# PCR_Main_ckt.net
KiCad netlist of a schematic drawn in EAGLE
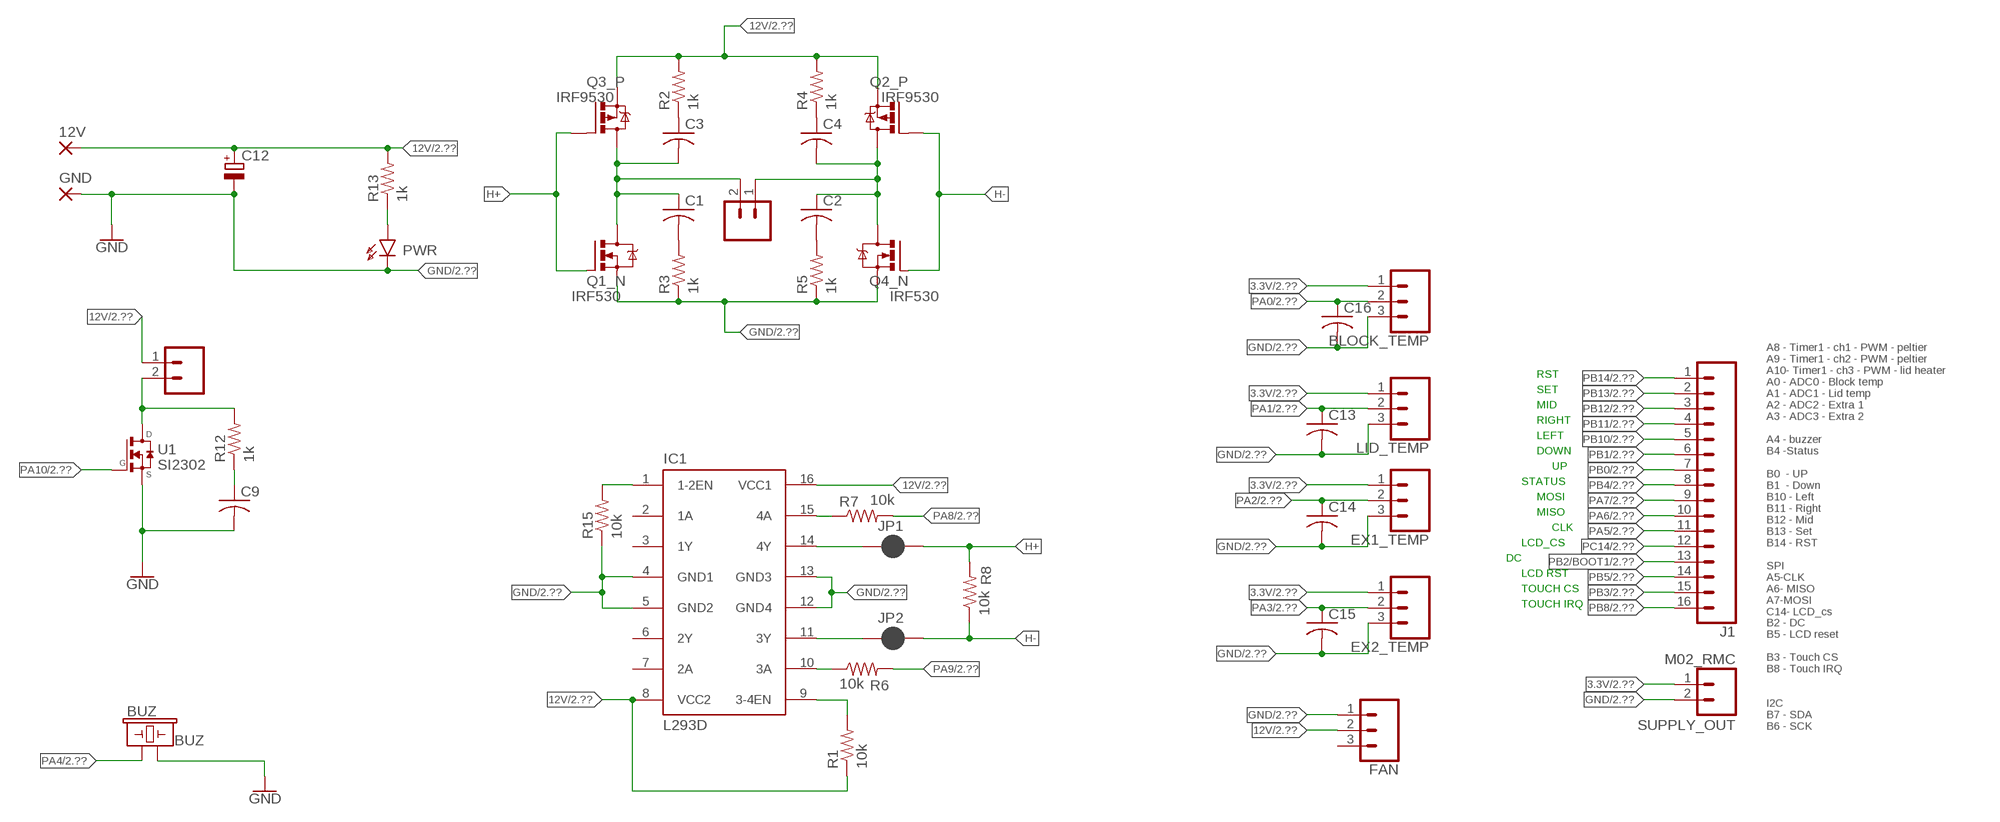
[diagram p0: schematic, sheet 1]
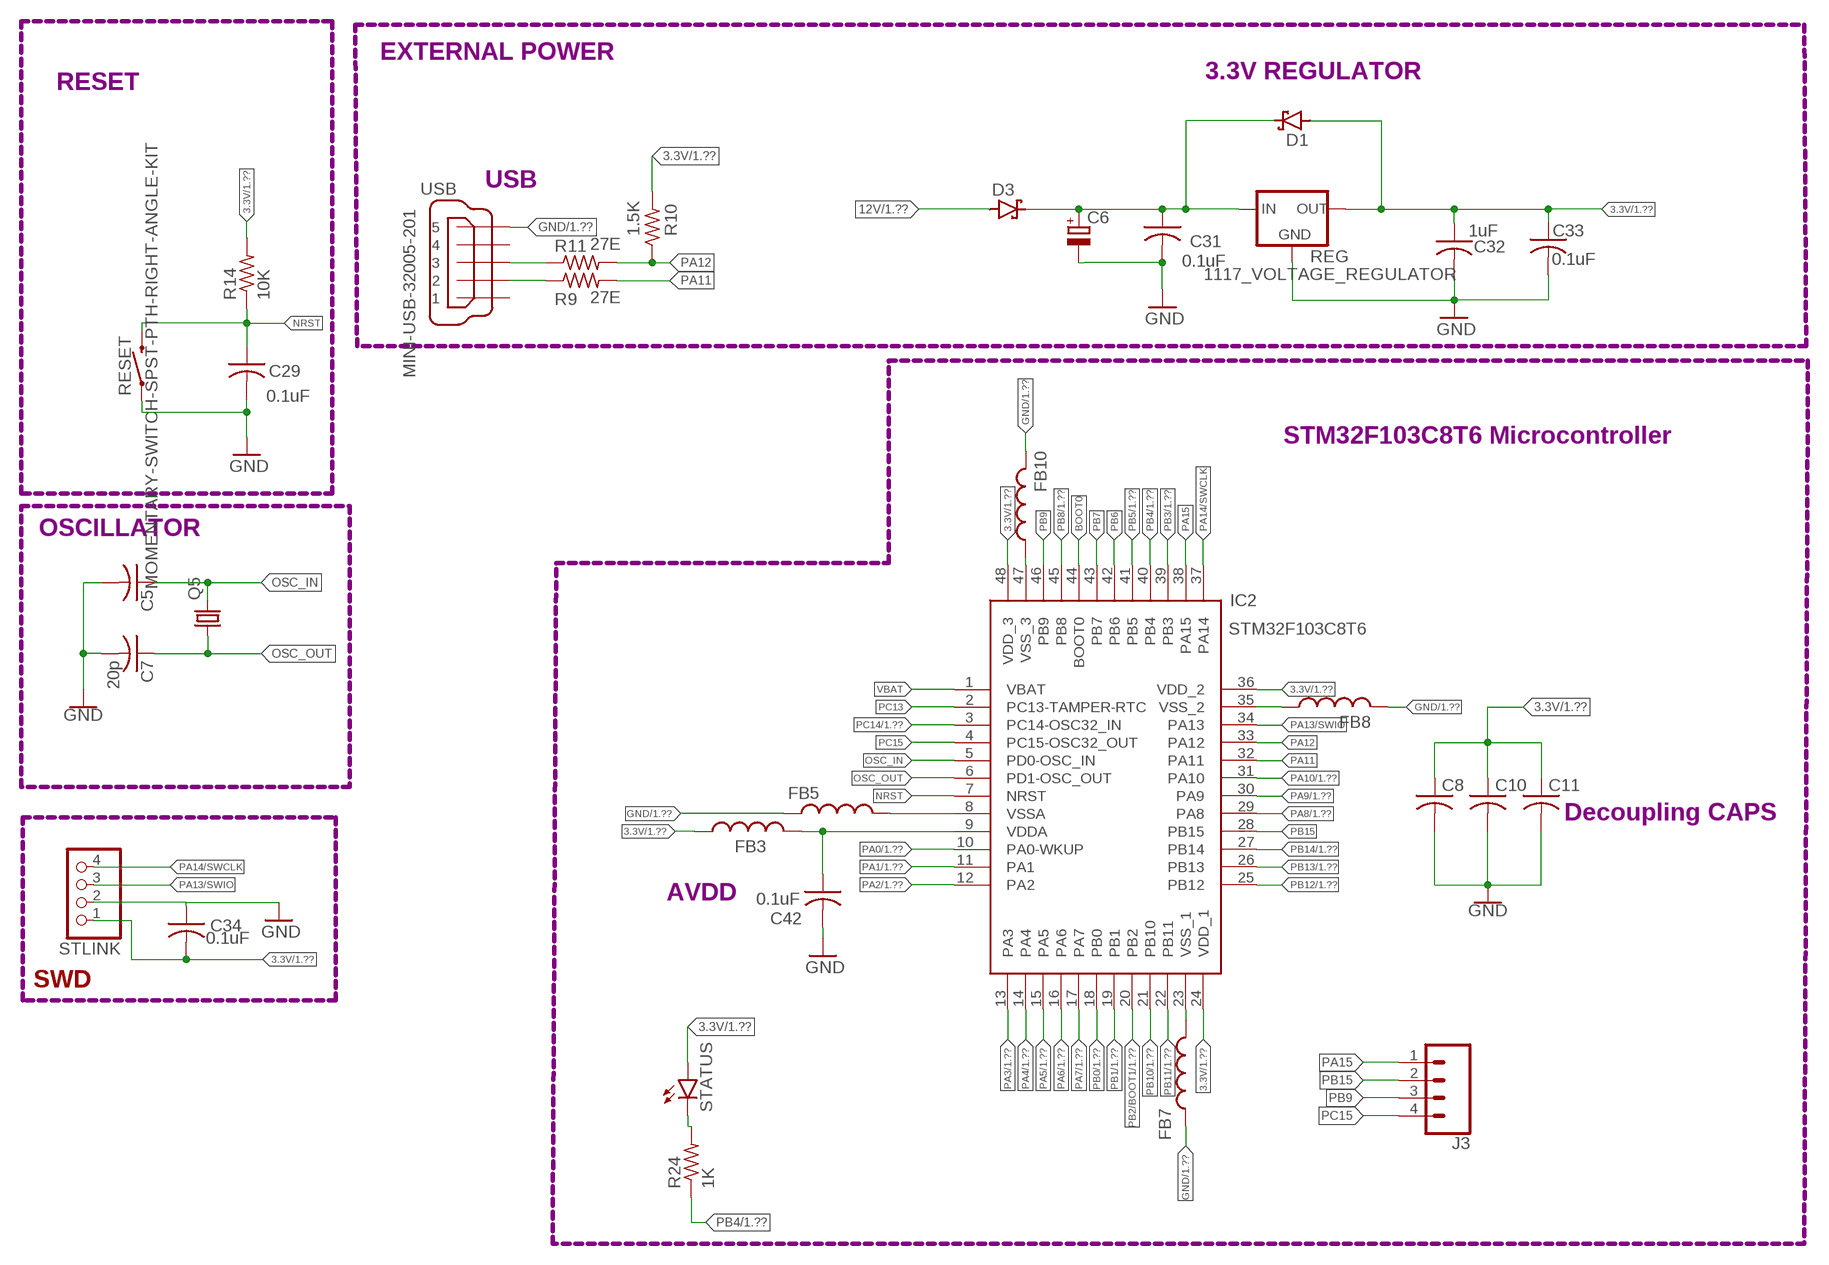
[diagram p1: schematic, sheet 2]

(export (version "E")
  (design (tool "Eeschema 10.0.6"))
  (components
    (comp (ref "+PELTIER-")
      (value "SCREW_TERMINAL_5.08")
      (footprint "eagle-import:SCREW_TERMINAL_5.08")
      (libsource (lib "eagle-import") (part "SCREW_TERMINAL_5.08"))
    )
    (comp (ref "12V")
      (value "WIREPAD4,16O1,6")
      (footprint "eagle-import:4,16O1,6")
      (libsource (lib "eagle-import") (part "WIREPAD4,16O1,6"))
    )
    (comp (ref "BLOCK_TEMP")
      (value "CONN_03")
      (footprint "eagle-import:1X03")
      (libsource (lib "eagle-import") (part "CONN_03"))
    )
    (comp (ref "BUZ")
      (value "BUZ")
      (footprint "eagle-import:BUZZER-12MM")
      (libsource (lib "eagle-import") (part "BUZZER-PTH"))
    )
    (comp (ref "C1")
      (value "C-USC0805")
      (footprint "eagle-import:C0805")
      (libsource (lib "eagle-import") (part "C-USC0805"))
    )
    (comp (ref "C2")
      (value "C-USC0805")
      (footprint "eagle-import:C0805")
      (libsource (lib "eagle-import") (part "C-USC0805"))
    )
    (comp (ref "C3")
      (value "C-USC0805")
      (footprint "eagle-import:C0805")
      (libsource (lib "eagle-import") (part "C-USC0805"))
    )
    (comp (ref "C4")
      (value "C-USC0805")
      (footprint "eagle-import:C0805")
      (libsource (lib "eagle-import") (part "C-USC0805"))
    )
    (comp (ref "C9")
      (value "C-USC0805")
      (footprint "eagle-import:C0805")
      (libsource (lib "eagle-import") (part "C-USC0805"))
    )
    (comp (ref "C12")
      (value "CPOL-EUE5-5")
      (footprint "eagle-import:E5-5")
      (libsource (lib "eagle-import") (part "CPOL-EUE5-5"))
    )
    (comp (ref "C13")
      (value "C-USC0805")
      (footprint "eagle-import:C0805")
      (libsource (lib "eagle-import") (part "C-USC0805"))
    )
    (comp (ref "C14")
      (value "C-USC0805")
      (footprint "eagle-import:C0805")
      (libsource (lib "eagle-import") (part "C-USC0805"))
    )
    (comp (ref "C15")
      (value "C-USC0805")
      (footprint "eagle-import:C0805")
      (libsource (lib "eagle-import") (part "C-USC0805"))
    )
    (comp (ref "C16")
      (value "C-USC0805")
      (footprint "eagle-import:C0805")
      (libsource (lib "eagle-import") (part "C-USC0805"))
    )
    (comp (ref "EX1_TEMP")
      (value "CONN_03")
      (footprint "eagle-import:1X03")
      (libsource (lib "eagle-import") (part "CONN_03"))
    )
    (comp (ref "EX2_TEMP")
      (value "CONN_03")
      (footprint "eagle-import:1X03")
      (libsource (lib "eagle-import") (part "CONN_03"))
    )
    (comp (ref "FAN")
      (value "CONN_03")
      (footprint "eagle-import:1X03")
      (libsource (lib "eagle-import") (part "CONN_03"))
    )
    (comp (ref "GND")
      (value "WIREPAD4,16O1,6")
      (footprint "eagle-import:4,16O1,6")
      (libsource (lib "eagle-import") (part "WIREPAD4,16O1,6"))
    )
    (comp (ref "IC1")
      (value "L293D")
      (footprint "eagle-import:DIL16")
      (libsource (lib "eagle-import") (part "L293D"))
    )
    (comp (ref "J1")
      (value "CONN_16")
      (footprint "eagle-import:1X16")
      (libsource (lib "eagle-import") (part "CONN_16"))
    )
    (comp (ref "JP1")
      (value "JUMPER-SMT_2_NC_PASTE_SILK")
      (footprint "eagle-import:SMT-JUMPER_2_NC_PASTE_SILK")
      (libsource (lib "eagle-import") (part "JUMPER-SMT_2_NC_PASTE_SILK"))
    )
    (comp (ref "JP2")
      (value "JUMPER-SMT_2_NC_PASTE_SILK")
      (footprint "eagle-import:SMT-JUMPER_2_NC_PASTE_SILK")
      (libsource (lib "eagle-import") (part "JUMPER-SMT_2_NC_PASTE_SILK"))
    )
    (comp (ref "LID_HEATER")
      (value "SCREW_TERMINAL_5.08")
      (footprint "eagle-import:SCREW_TERMINAL_5.08")
      (libsource (lib "eagle-import") (part "SCREW_TERMINAL_5.08"))
    )
    (comp (ref "LID_TEMP")
      (value "CONN_03")
      (footprint "eagle-import:1X03")
      (libsource (lib "eagle-import") (part "CONN_03"))
    )
    (comp (ref "PWR")
      (value "LED_RED_0805")
      (footprint "eagle-import:RED_LED")
      (libsource (lib "eagle-import") (part "LED_RED_0805"))
    )
    (comp (ref "Q1_N")
      (value "IRF530")
      (footprint "eagle-import:TO220BV")
      (libsource (lib "eagle-import") (part "IRF530"))
    )
    (comp (ref "Q2_P")
      (value "IRF9530")
      (footprint "eagle-import:TO220BV")
      (libsource (lib "eagle-import") (part "IRF9530"))
    )
    (comp (ref "Q3_P")
      (value "IRF9530")
      (footprint "eagle-import:TO220BV")
      (libsource (lib "eagle-import") (part "IRF9530"))
    )
    (comp (ref "Q4_N")
      (value "IRF530")
      (footprint "eagle-import:TO220BV")
      (libsource (lib "eagle-import") (part "IRF530"))
    )
    (comp (ref "R1")
      (value "10k")
      (footprint "eagle-import:R0805")
      (libsource (lib "eagle-import") (part "R-US_R0805"))
    )
    (comp (ref "R2")
      (value "1k")
      (footprint "eagle-import:R0805")
      (libsource (lib "eagle-import") (part "R-US_R0805"))
    )
    (comp (ref "R3")
      (value "1k")
      (footprint "eagle-import:R0805")
      (libsource (lib "eagle-import") (part "R-US_R0805"))
    )
    (comp (ref "R4")
      (value "1k")
      (footprint "eagle-import:R0805")
      (libsource (lib "eagle-import") (part "R-US_R0805"))
    )
    (comp (ref "R5")
      (value "1k")
      (footprint "eagle-import:R0805")
      (libsource (lib "eagle-import") (part "R-US_R0805"))
    )
    (comp (ref "R6")
      (value "10k")
      (footprint "eagle-import:R0805")
      (libsource (lib "eagle-import") (part "R-US_R0805"))
    )
    (comp (ref "R7")
      (value "10k")
      (footprint "eagle-import:R0805")
      (libsource (lib "eagle-import") (part "R-US_R0805"))
    )
    (comp (ref "R8")
      (value "10k")
      (footprint "eagle-import:R0805")
      (libsource (lib "eagle-import") (part "R-US_R0805"))
    )
    (comp (ref "R12")
      (value "1k")
      (footprint "eagle-import:R0805")
      (libsource (lib "eagle-import") (part "R-US_R0805"))
    )
    (comp (ref "R13")
      (value "1k")
      (footprint "eagle-import:R0805")
      (libsource (lib "eagle-import") (part "R-US_R0805"))
    )
    (comp (ref "R15")
      (value "10k")
      (footprint "eagle-import:R0805")
      (libsource (lib "eagle-import") (part "R-US_R0805"))
    )
    (comp (ref "SUPPLY_OUT")
      (value "M02_RMC")
      (footprint "eagle-import:M02_RMC")
      (libsource (lib "eagle-import") (part "M02_RMC"))
    )
    (comp (ref "U1")
      (value "SI2302")
      (footprint "eagle-import:SOT95P240X110-3N")
      (libsource (lib "eagle-import") (part "SI2302"))
    )
    (comp (ref "C5")
      (value "C-USC0805")
      (footprint "eagle-import:C0805")
      (libsource (lib "eagle-import") (part "C-USC0805"))
    )
    (comp (ref "C6")
      (value "CPOL-EUE5-5")
      (footprint "eagle-import:E5-5")
      (libsource (lib "eagle-import") (part "CPOL-EUE5-5"))
    )
    (comp (ref "C7")
      (value "20p")
      (footprint "eagle-import:C0805")
      (libsource (lib "eagle-import") (part "C-USC0805"))
    )
    (comp (ref "C8")
      (value "C-USC0805")
      (footprint "eagle-import:C0805")
      (libsource (lib "eagle-import") (part "C-USC0805"))
    )
    (comp (ref "C10")
      (value "C-USC0805")
      (footprint "eagle-import:C0805")
      (libsource (lib "eagle-import") (part "C-USC0805"))
    )
    (comp (ref "C11")
      (value "C-USC0805")
      (footprint "eagle-import:C0805")
      (libsource (lib "eagle-import") (part "C-USC0805"))
    )
    (comp (ref "C29")
      (value "0.1uF")
      (footprint "eagle-import:C0603")
      (libsource (lib "eagle-import") (part "rcl_C-USC0603"))
    )
    (comp (ref "C31")
      (value "0.1uF")
      (footprint "eagle-import:C0603")
      (libsource (lib "eagle-import") (part "rcl_C-USC0603"))
    )
    (comp (ref "C32")
      (value "1uF")
      (footprint "eagle-import:C0603")
      (libsource (lib "eagle-import") (part "C-USC0603"))
    )
    (comp (ref "C33")
      (value "0.1uF")
      (footprint "eagle-import:C0603")
      (libsource (lib "eagle-import") (part "rcl_C-USC0603"))
    )
    (comp (ref "C34")
      (value "0.1uF")
      (footprint "eagle-import:C0603")
      (libsource (lib "eagle-import") (part "rcl_C-USC0603"))
    )
    (comp (ref "C42")
      (value "0.1uF")
      (footprint "eagle-import:C0603")
      (libsource (lib "eagle-import") (part "rcl_C-USC0603"))
    )
    (comp (ref "D1")
      (value "SCHOTTKY-DIODESMD")
      (footprint "eagle-import:SMB")
      (libsource (lib "eagle-import") (part "SCHOTTKY-DIODESMD"))
    )
    (comp (ref "D3")
      (value "SCHOTTKY-DIODESMD")
      (footprint "eagle-import:SMB")
      (libsource (lib "eagle-import") (part "SCHOTTKY-DIODESMD"))
    )
    (comp (ref "FB3")
      (value "FERRITE-BEADA")
      (footprint "eagle-import:0603")
      (libsource (lib "eagle-import") (part "FERRITE-BEADA"))
    )
    (comp (ref "FB5")
      (value "FERRITE-BEADA")
      (footprint "eagle-import:0603")
      (libsource (lib "eagle-import") (part "FERRITE-BEADA"))
    )
    (comp (ref "FB7")
      (value "FERRITE-BEADA")
      (footprint "eagle-import:0603")
      (libsource (lib "eagle-import") (part "FERRITE-BEADA"))
    )
    (comp (ref "FB8")
      (value "FERRITE-BEADA")
      (footprint "eagle-import:0603")
      (libsource (lib "eagle-import") (part "FERRITE-BEADA"))
    )
    (comp (ref "FB10")
      (value "FERRITE-BEADA")
      (footprint "eagle-import:0603")
      (libsource (lib "eagle-import") (part "FERRITE-BEADA"))
    )
    (comp (ref "IC2")
      (value "STM32F103C8T6")
      (footprint "eagle-import:QFP50P900X900X160-48N")
      (fields
        (field (name "MANUFACTURER_PART_NUMBER") "stm32f103c8t6")
        (field (name "MOUSER_PART_NUMBER") "511-STM32F103C8T6")
      )
      (libsource (lib "eagle-import") (part "STM32F103C8T6"))
    )
    (comp (ref "J3")
      (value "F04_LOCKLOCK")
      (footprint "eagle-import:F04_LOCK")
      (libsource (lib "eagle-import") (part "F04_LOCKLOCK"))
    )
    (comp (ref "Q5")
      (value "CRYSTALHC49S")
      (footprint "eagle-import:HC49_S")
      (libsource (lib "eagle-import") (part "CRYSTALHC49S"))
    )
    (comp (ref "R9")
      (value "27E")
      (footprint "eagle-import:R0805")
      (libsource (lib "eagle-import") (part "R-US_R0805"))
    )
    (comp (ref "R10")
      (value "1.5K")
      (footprint "eagle-import:R0805")
      (libsource (lib "eagle-import") (part "R-US_R0805"))
    )
    (comp (ref "R11")
      (value "27E")
      (footprint "eagle-import:R0805")
      (libsource (lib "eagle-import") (part "R-US_R0805"))
    )
    (comp (ref "R14")
      (value "10K")
      (footprint "eagle-import:R0603")
      (libsource (lib "eagle-import") (part "rcl_R-US_R0603"))
    )
    (comp (ref "R24")
      (value "1K")
      (footprint "eagle-import:R0603")
      (libsource (lib "eagle-import") (part "rcl_R-US_R0603"))
    )
    (comp (ref "REG")
      (value "1117_VOLTAGE_REGULATOR")
      (footprint "eagle-import:SOT230P700X180-4N")
      (libsource (lib "eagle-import") (part "1117_VOLTAGE_REGULATOR"))
    )
    (comp (ref "RESET")
      (value "MOMENTARY-SWITCH-SPST-PTH-RIGHT-ANGLE-KIT")
      (footprint "eagle-import:TACTILE_SWITCH_PTH_RIGHT_ANGLE_KIT")
      (libsource (lib "eagle-import") (part "MOMENTARY-SWITCH-SPST-PTH-RIGHT-ANGLE-KIT"))
    )
    (comp (ref "STATUS")
      (value "LEDCHIP-LED0603")
      (footprint "eagle-import:CHIP-LED0603")
      (libsource (lib "eagle-import") (part "LEDCHIP-LED0603"))
    )
    (comp (ref "STLINK")
      (value "PINHD-1X4")
      (footprint "eagle-import:1X04")
      (libsource (lib "eagle-import") (part "PINHD-1X4"))
    )
    (comp (ref "USB")
      (value "MINI-USB-32005-201")
      (footprint "eagle-import:32005-201")
      (libsource (lib "eagle-import") (part "MINI-USB-32005-201"))
    )
  )
  (nets
    (net (code "1") (name "3.3V") (class "Default")
      (node (ref "BLOCK_TEMP") (pin "1") (pinfunction "1_1") (pintype "passive"))
      (node (ref "C10") (pin "1") (pinfunction "1_1") (pintype "passive"))
      (node (ref "C11") (pin "1") (pinfunction "1_1") (pintype "passive"))
      (node (ref "C32") (pin "1") (pinfunction "1_1") (pintype "passive"))
      (node (ref "C33") (pin "1") (pinfunction "1_1") (pintype "passive"))
      (node (ref "C34") (pin "2") (pinfunction "2_2") (pintype "passive"))
      (node (ref "C8") (pin "1") (pinfunction "1_1") (pintype "passive"))
      (node (ref "D1") (pin "A") (pinfunction "A_A") (pintype "passive"))
      (node (ref "EX1_TEMP") (pin "1") (pinfunction "1_1") (pintype "passive"))
      (node (ref "EX2_TEMP") (pin "1") (pinfunction "1_1") (pintype "passive"))
      (node (ref "FB3") (pin "1") (pinfunction "1_1") (pintype "passive"))
      (node (ref "IC2") (pin "24") (pinfunction "VDD_1_24") (pintype "bidirectional"))
      (node (ref "IC2") (pin "36") (pinfunction "VDD_2_36") (pintype "bidirectional"))
      (node (ref "IC2") (pin "48") (pinfunction "VDD_3_48") (pintype "bidirectional"))
      (node (ref "LID_TEMP") (pin "1") (pinfunction "1_1") (pintype "passive"))
      (node (ref "R10") (pin "2") (pinfunction "2_2") (pintype "passive"))
      (node (ref "R14") (pin "2") (pinfunction "2_2") (pintype "passive"))
      (node (ref "REG") (pin "2") (pinfunction "OUT_2") (pintype "passive"))
      (node (ref "REG") (pin "4") (pinfunction "OUT_4") (pintype "passive"))
      (node (ref "STATUS") (pin "A") (pinfunction "A_A") (pintype "passive"))
      (node (ref "STLINK") (pin "1") (pinfunction "1_1") (pintype "passive"))
      (node (ref "SUPPLY_OUT") (pin "1") (pinfunction "1_1") (pintype "passive"))
    )
    (net (code "2") (name "12V") (class "Default")
      (node (ref "12V") (pin "1") (pinfunction "P_1") (pintype "passive"))
      (node (ref "C12") (pin "+") (pinfunction "+_+") (pintype "passive"))
      (node (ref "D3") (pin "A") (pinfunction "A_A") (pintype "passive"))
      (node (ref "FAN") (pin "2") (pinfunction "2_2") (pintype "passive"))
      (node (ref "IC1") (pin "16") (pinfunction "VCC1_16") (pintype "power_in"))
      (node (ref "IC1") (pin "8") (pinfunction "VCC2_8") (pintype "power_in"))
      (node (ref "LID_HEATER") (pin "1") (pinfunction "1_1") (pintype "passive"))
      (node (ref "Q2_P") (pin "S") (pinfunction "S_S") (pintype "passive"))
      (node (ref "Q3_P") (pin "S") (pinfunction "S_S") (pintype "passive"))
      (node (ref "R1") (pin "1") (pinfunction "1_1") (pintype "passive"))
      (node (ref "R13") (pin "2") (pinfunction "2_2") (pintype "passive"))
      (node (ref "R2") (pin "2") (pinfunction "2_2") (pintype "passive"))
      (node (ref "R4") (pin "2") (pinfunction "2_2") (pintype "passive"))
    )
    (net (code "3") (name "BOOT0") (class "Default")
      (node (ref "IC2") (pin "44") (pinfunction "BOOT0_44") (pintype "bidirectional"))
    )
    (net (code "4") (name "GND") (class "Default")
      (node (ref "BLOCK_TEMP") (pin "3") (pinfunction "3_3") (pintype "passive"))
      (node (ref "BUZ") (pin "-") (pinfunction "2_-") (pintype "passive"))
      (node (ref "C10") (pin "2") (pinfunction "2_2") (pintype "passive"))
      (node (ref "C11") (pin "2") (pinfunction "2_2") (pintype "passive"))
      (node (ref "C12") (pin "-") (pinfunction "-_-") (pintype "passive"))
      (node (ref "C13") (pin "2") (pinfunction "2_2") (pintype "passive"))
      (node (ref "C14") (pin "2") (pinfunction "2_2") (pintype "passive"))
      (node (ref "C15") (pin "2") (pinfunction "2_2") (pintype "passive"))
      (node (ref "C16") (pin "2") (pinfunction "2_2") (pintype "passive"))
      (node (ref "C29") (pin "2") (pinfunction "2_2") (pintype "passive"))
      (node (ref "C31") (pin "2") (pinfunction "2_2") (pintype "passive"))
      (node (ref "C32") (pin "2") (pinfunction "2_2") (pintype "passive"))
      (node (ref "C33") (pin "2") (pinfunction "2_2") (pintype "passive"))
      (node (ref "C34") (pin "1") (pinfunction "1_1") (pintype "passive"))
      (node (ref "C42") (pin "2") (pinfunction "2_2") (pintype "passive"))
      (node (ref "C5") (pin "2") (pinfunction "2_2") (pintype "passive"))
      (node (ref "C6") (pin "-") (pinfunction "-_-") (pintype "passive"))
      (node (ref "C7") (pin "2") (pinfunction "2_2") (pintype "passive"))
      (node (ref "C8") (pin "2") (pinfunction "2_2") (pintype "passive"))
      (node (ref "C9") (pin "2") (pinfunction "2_2") (pintype "passive"))
      (node (ref "EX1_TEMP") (pin "3") (pinfunction "3_3") (pintype "passive"))
      (node (ref "EX2_TEMP") (pin "3") (pinfunction "3_3") (pintype "passive"))
      (node (ref "FAN") (pin "1") (pinfunction "1_1") (pintype "passive"))
      (node (ref "FB10") (pin "2") (pinfunction "2_2") (pintype "passive"))
      (node (ref "FB5") (pin "1") (pinfunction "1_1") (pintype "passive"))
      (node (ref "FB7") (pin "1") (pinfunction "1_1") (pintype "passive"))
      (node (ref "FB8") (pin "2") (pinfunction "2_2") (pintype "passive"))
      (node (ref "GND") (pin "1") (pinfunction "P_1") (pintype "passive"))
      (node (ref "IC1") (pin "12") (pinfunction "GND4_12") (pintype "power_in"))
      (node (ref "IC1") (pin "13") (pinfunction "GND3_13") (pintype "power_in"))
      (node (ref "IC1") (pin "4") (pinfunction "GND1_4") (pintype "power_in"))
      (node (ref "IC1") (pin "5") (pinfunction "GND2_5") (pintype "power_in"))
      (node (ref "LID_TEMP") (pin "3") (pinfunction "3_3") (pintype "passive"))
      (node (ref "PWR") (pin "2") (pinfunction "C_2") (pintype "passive"))
      (node (ref "Q1_N") (pin "S") (pinfunction "S_S") (pintype "passive"))
      (node (ref "Q4_N") (pin "S") (pinfunction "S_S") (pintype "passive"))
      (node (ref "R15") (pin "1") (pinfunction "1_1") (pintype "passive"))
      (node (ref "R3") (pin "1") (pinfunction "1_1") (pintype "passive"))
      (node (ref "R5") (pin "1") (pinfunction "1_1") (pintype "passive"))
      (node (ref "REG") (pin "1") (pinfunction "GND_1") (pintype "input"))
      (node (ref "RESET") (pin "1") (pinfunction "1_1") (pintype "passive"))
      (node (ref "STLINK") (pin "2") (pinfunction "2_2") (pintype "passive"))
      (node (ref "SUPPLY_OUT") (pin "2") (pinfunction "2_2") (pintype "passive"))
      (node (ref "U1") (pin "2") (pinfunction "S_2") (pintype "passive"))
      (node (ref "USB") (pin "5") (pinfunction "5_5") (pintype "passive"))
    )
    (net (code "5") (name "H+") (class "Default")
      (node (ref "JP1") (pin "2") (pinfunction "2_2") (pintype "passive"))
      (node (ref "Q1_N") (pin "G") (pinfunction "G_G") (pintype "passive"))
      (node (ref "Q3_P") (pin "G") (pinfunction "G_G") (pintype "passive"))
      (node (ref "R8") (pin "2") (pinfunction "2_2") (pintype "passive"))
    )
    (net (code "6") (name "H-") (class "Default")
      (node (ref "JP2") (pin "2") (pinfunction "2_2") (pintype "passive"))
      (node (ref "Q2_P") (pin "G") (pinfunction "G_G") (pintype "passive"))
      (node (ref "Q4_N") (pin "G") (pinfunction "G_G") (pintype "passive"))
      (node (ref "R8") (pin "1") (pinfunction "1_1") (pintype "passive"))
    )
    (net (code "7") (name "NRST") (class "Default")
      (node (ref "C29") (pin "1") (pinfunction "1_1") (pintype "passive"))
      (node (ref "IC2") (pin "7") (pinfunction "NRST_7") (pintype "bidirectional"))
      (node (ref "R14") (pin "1") (pinfunction "1_1") (pintype "passive"))
      (node (ref "RESET") (pin "2") (pinfunction "2_2") (pintype "passive"))
    )
    (net (code "8") (name "Net-(+PELTIER--Pad1)") (class "Default")
      (node (ref "+PELTIER-") (pin "1") (pinfunction "1_1") (pintype "passive"))
      (node (ref "C2") (pin "1") (pinfunction "1_1") (pintype "passive"))
      (node (ref "C4") (pin "2") (pinfunction "2_2") (pintype "passive"))
      (node (ref "Q2_P") (pin "D") (pinfunction "D_D") (pintype "passive"))
      (node (ref "Q4_N") (pin "D") (pinfunction "D_D") (pintype "passive"))
    )
    (net (code "9") (name "Net-(+PELTIER--Pad2)") (class "Default")
      (node (ref "+PELTIER-") (pin "2") (pinfunction "2_2") (pintype "passive"))
      (node (ref "C1") (pin "1") (pinfunction "1_1") (pintype "passive"))
      (node (ref "C3") (pin "2") (pinfunction "2_2") (pintype "passive"))
      (node (ref "Q1_N") (pin "D") (pinfunction "D_D") (pintype "passive"))
      (node (ref "Q3_P") (pin "D") (pinfunction "D_D") (pintype "passive"))
    )
    (net (code "10") (name "Net-(C1-Pad2)") (class "Default")
      (node (ref "C1") (pin "2") (pinfunction "2_2") (pintype "passive"))
      (node (ref "R3") (pin "2") (pinfunction "2_2") (pintype "passive"))
    )
    (net (code "11") (name "Net-(C2-Pad2)") (class "Default")
      (node (ref "C2") (pin "2") (pinfunction "2_2") (pintype "passive"))
      (node (ref "R5") (pin "2") (pinfunction "2_2") (pintype "passive"))
    )
    (net (code "12") (name "Net-(C3-Pad1)") (class "Default")
      (node (ref "C3") (pin "1") (pinfunction "1_1") (pintype "passive"))
      (node (ref "R2") (pin "1") (pinfunction "1_1") (pintype "passive"))
    )
    (net (code "13") (name "Net-(C4-Pad1)") (class "Default")
      (node (ref "C4") (pin "1") (pinfunction "1_1") (pintype "passive"))
      (node (ref "R4") (pin "1") (pinfunction "1_1") (pintype "passive"))
    )
    (net (code "14") (name "Net-(C9-Pad1)") (class "Default")
      (node (ref "C9") (pin "1") (pinfunction "1_1") (pintype "passive"))
      (node (ref "R12") (pin "1") (pinfunction "1_1") (pintype "passive"))
    )
    (net (code "15") (name "Net-(IC1-1-2EN)") (class "Default")
      (node (ref "IC1") (pin "1") (pinfunction "1-2EN_1") (pintype "input"))
      (node (ref "R15") (pin "2") (pinfunction "2_2") (pintype "passive"))
    )
    (net (code "16") (name "Net-(IC1-3-4EN)") (class "Default")
      (node (ref "IC1") (pin "9") (pinfunction "3-4EN_9") (pintype "input"))
      (node (ref "R1") (pin "2") (pinfunction "2_2") (pintype "passive"))
    )
    (net (code "17") (name "Net-(IC1-3A)") (class "Default")
      (node (ref "IC1") (pin "10") (pinfunction "3A_10") (pintype "input"))
      (node (ref "R6") (pin "1") (pinfunction "1_1") (pintype "passive"))
    )
    (net (code "18") (name "Net-(IC1-3Y)") (class "Default")
      (node (ref "IC1") (pin "11") (pinfunction "3Y_11") (pintype "output"))
      (node (ref "JP2") (pin "1") (pinfunction "1_1") (pintype "passive"))
    )
    (net (code "19") (name "Net-(IC1-4A)") (class "Default")
      (node (ref "IC1") (pin "15") (pinfunction "4A_15") (pintype "input"))
      (node (ref "R7") (pin "1") (pinfunction "1_1") (pintype "passive"))
    )
    (net (code "20") (name "Net-(IC1-4Y)") (class "Default")
      (node (ref "IC1") (pin "14") (pinfunction "4Y_14") (pintype "output"))
      (node (ref "JP1") (pin "1") (pinfunction "1_1") (pintype "passive"))
    )
    (net (code "21") (name "Net-(IC2-VDDA)") (class "Default")
      (node (ref "C42") (pin "1") (pinfunction "1_1") (pintype "passive"))
      (node (ref "FB3") (pin "2") (pinfunction "2_2") (pintype "passive"))
      (node (ref "IC2") (pin "9") (pinfunction "VDDA_9") (pintype "bidirectional"))
    )
    (net (code "22") (name "Net-(IC2-VSSA)") (class "Default")
      (node (ref "FB5") (pin "2") (pinfunction "2_2") (pintype "passive"))
      (node (ref "IC2") (pin "8") (pinfunction "VSSA_8") (pintype "bidirectional"))
    )
    (net (code "23") (name "Net-(IC2-VSS_1)") (class "Default")
      (node (ref "FB7") (pin "2") (pinfunction "2_2") (pintype "passive"))
      (node (ref "IC2") (pin "23") (pinfunction "VSS_1_23") (pintype "bidirectional"))
    )
    (net (code "24") (name "Net-(IC2-VSS_2)") (class "Default")
      (node (ref "FB8") (pin "1") (pinfunction "1_1") (pintype "passive"))
      (node (ref "IC2") (pin "35") (pinfunction "VSS_2_35") (pintype "bidirectional"))
    )
    (net (code "25") (name "Net-(IC2-VSS_3)") (class "Default")
      (node (ref "FB10") (pin "1") (pinfunction "1_1") (pintype "passive"))
      (node (ref "IC2") (pin "47") (pinfunction "VSS_3_47") (pintype "bidirectional"))
    )
    (net (code "26") (name "Net-(PWR-A)") (class "Default")
      (node (ref "PWR") (pin "1") (pinfunction "A_1") (pintype "passive"))
      (node (ref "R13") (pin "1") (pinfunction "1_1") (pintype "passive"))
    )
    (net (code "27") (name "Net-(R9-Pad1)") (class "Default")
      (node (ref "R9") (pin "1") (pinfunction "1_1") (pintype "passive"))
      (node (ref "USB") (pin "2") (pinfunction "2_2") (pintype "passive"))
    )
    (net (code "28") (name "Net-(R11-Pad1)") (class "Default")
      (node (ref "R11") (pin "1") (pinfunction "1_1") (pintype "passive"))
      (node (ref "USB") (pin "3") (pinfunction "3_3") (pintype "passive"))
    )
    (net (code "29") (name "Net-(R24-Pad2)") (class "Default")
      (node (ref "R24") (pin "2") (pinfunction "2_2") (pintype "passive"))
      (node (ref "STATUS") (pin "C") (pinfunction "C_C") (pintype "passive"))
    )
    (net (code "30") (name "Net-(REG-IN)") (class "Default")
      (node (ref "C31") (pin "1") (pinfunction "1_1") (pintype "passive"))
      (node (ref "C6") (pin "+") (pinfunction "+_+") (pintype "passive"))
      (node (ref "D1") (pin "C") (pinfunction "C_C") (pintype "passive"))
      (node (ref "D3") (pin "C") (pinfunction "C_C") (pintype "passive"))
      (node (ref "REG") (pin "3") (pinfunction "IN_3") (pintype "input"))
    )
    (net (code "31") (name "Net-(U1-D)") (class "Default")
      (node (ref "LID_HEATER") (pin "2") (pinfunction "2_2") (pintype "passive"))
      (node (ref "R12") (pin "2") (pinfunction "2_2") (pintype "passive"))
      (node (ref "U1") (pin "3") (pinfunction "D_3") (pintype "passive"))
    )
    (net (code "32") (name "OSC_IN") (class "Default")
      (node (ref "C5") (pin "1") (pinfunction "1_1") (pintype "passive"))
      (node (ref "IC2") (pin "5") (pinfunction "PD0-OSC_IN_5") (pintype "bidirectional"))
      (node (ref "Q5") (pin "2") (pinfunction "2_2") (pintype "passive"))
    )
    (net (code "33") (name "OSC_OUT") (class "Default")
      (node (ref "C7") (pin "1") (pinfunction "1_1") (pintype "passive"))
      (node (ref "IC2") (pin "6") (pinfunction "PD1-OSC_OUT_6") (pintype "bidirectional"))
      (node (ref "Q5") (pin "1") (pinfunction "1_1") (pintype "passive"))
    )
    (net (code "34") (name "PA0") (class "Default")
      (node (ref "BLOCK_TEMP") (pin "2") (pinfunction "2_2") (pintype "passive"))
      (node (ref "C16") (pin "1") (pinfunction "1_1") (pintype "passive"))
      (node (ref "IC2") (pin "10") (pinfunction "PA0-WKUP_10") (pintype "bidirectional"))
    )
    (net (code "35") (name "PA1") (class "Default")
      (node (ref "C13") (pin "1") (pinfunction "1_1") (pintype "passive"))
      (node (ref "IC2") (pin "11") (pinfunction "PA1_11") (pintype "bidirectional"))
      (node (ref "LID_TEMP") (pin "2") (pinfunction "2_2") (pintype "passive"))
    )
    (net (code "36") (name "PA2") (class "Default")
      (node (ref "C14") (pin "1") (pinfunction "1_1") (pintype "passive"))
      (node (ref "EX1_TEMP") (pin "2") (pinfunction "2_2") (pintype "passive"))
      (node (ref "IC2") (pin "12") (pinfunction "PA2_12") (pintype "bidirectional"))
    )
    (net (code "37") (name "PA3") (class "Default")
      (node (ref "C15") (pin "1") (pinfunction "1_1") (pintype "passive"))
      (node (ref "EX2_TEMP") (pin "2") (pinfunction "2_2") (pintype "passive"))
      (node (ref "IC2") (pin "13") (pinfunction "PA3_13") (pintype "bidirectional"))
    )
    (net (code "38") (name "PA4") (class "Default")
      (node (ref "BUZ") (pin "+") (pinfunction "1_+") (pintype "passive"))
      (node (ref "IC2") (pin "14") (pinfunction "PA4_14") (pintype "bidirectional"))
    )
    (net (code "39") (name "PA5") (class "Default")
      (node (ref "IC2") (pin "15") (pinfunction "PA5_15") (pintype "bidirectional"))
      (node (ref "J1") (pin "11") (pinfunction "11_11") (pintype "passive"))
    )
    (net (code "40") (name "PA6") (class "Default")
      (node (ref "IC2") (pin "16") (pinfunction "PA6_16") (pintype "bidirectional"))
      (node (ref "J1") (pin "10") (pinfunction "10_10") (pintype "passive"))
    )
    (net (code "41") (name "PA7") (class "Default")
      (node (ref "IC2") (pin "17") (pinfunction "PA7_17") (pintype "bidirectional"))
      (node (ref "J1") (pin "9") (pinfunction "9_9") (pintype "passive"))
    )
    (net (code "42") (name "PA8") (class "Default")
      (node (ref "IC2") (pin "29") (pinfunction "PA8_29") (pintype "bidirectional"))
      (node (ref "R7") (pin "2") (pinfunction "2_2") (pintype "passive"))
    )
    (net (code "43") (name "PA9") (class "Default")
      (node (ref "IC2") (pin "30") (pinfunction "PA9_30") (pintype "bidirectional"))
      (node (ref "R6") (pin "2") (pinfunction "2_2") (pintype "passive"))
    )
    (net (code "44") (name "PA10") (class "Default")
      (node (ref "IC2") (pin "31") (pinfunction "PA10_31") (pintype "bidirectional"))
      (node (ref "U1") (pin "1") (pinfunction "G_1") (pintype "passive"))
    )
    (net (code "45") (name "PA11") (class "Default")
      (node (ref "IC2") (pin "32") (pinfunction "PA11_32") (pintype "bidirectional"))
      (node (ref "R9") (pin "2") (pinfunction "2_2") (pintype "passive"))
    )
    (net (code "46") (name "PA12") (class "Default")
      (node (ref "IC2") (pin "33") (pinfunction "PA12_33") (pintype "bidirectional"))
      (node (ref "R10") (pin "1") (pinfunction "1_1") (pintype "passive"))
      (node (ref "R11") (pin "2") (pinfunction "2_2") (pintype "passive"))
    )
    (net (code "47") (name "PA13{slash}SWIO") (class "Default")
      (node (ref "IC2") (pin "34") (pinfunction "PA13_34") (pintype "bidirectional"))
      (node (ref "STLINK") (pin "3") (pinfunction "3_3") (pintype "passive"))
    )
    (net (code "48") (name "PA14{slash}SWCLK") (class "Default")
      (node (ref "IC2") (pin "37") (pinfunction "PA14_37") (pintype "bidirectional"))
      (node (ref "STLINK") (pin "4") (pinfunction "4_4") (pintype "passive"))
    )
    (net (code "49") (name "PA15") (class "Default")
      (node (ref "IC2") (pin "38") (pinfunction "PA15_38") (pintype "bidirectional"))
      (node (ref "J3") (pin "1") (pinfunction "1_1") (pintype "passive"))
    )
    (net (code "50") (name "PB0") (class "Default")
      (node (ref "IC2") (pin "18") (pinfunction "PB0_18") (pintype "bidirectional"))
      (node (ref "J1") (pin "7") (pinfunction "7_7") (pintype "passive"))
    )
    (net (code "51") (name "PB1") (class "Default")
      (node (ref "IC2") (pin "19") (pinfunction "PB1_19") (pintype "bidirectional"))
      (node (ref "J1") (pin "6") (pinfunction "6_6") (pintype "passive"))
    )
    (net (code "52") (name "PB2{slash}BOOT1") (class "Default")
      (node (ref "IC2") (pin "20") (pinfunction "PB2_20") (pintype "bidirectional"))
      (node (ref "J1") (pin "13") (pinfunction "13_13") (pintype "passive"))
    )
    (net (code "53") (name "PB3") (class "Default")
      (node (ref "IC2") (pin "39") (pinfunction "PB3_39") (pintype "bidirectional"))
      (node (ref "J1") (pin "15") (pinfunction "15_15") (pintype "passive"))
    )
    (net (code "54") (name "PB4") (class "Default")
      (node (ref "IC2") (pin "40") (pinfunction "PB4_40") (pintype "bidirectional"))
      (node (ref "J1") (pin "8") (pinfunction "8_8") (pintype "passive"))
      (node (ref "R24") (pin "1") (pinfunction "1_1") (pintype "passive"))
    )
    (net (code "55") (name "PB5") (class "Default")
      (node (ref "IC2") (pin "41") (pinfunction "PB5_41") (pintype "bidirectional"))
      (node (ref "J1") (pin "14") (pinfunction "14_14") (pintype "passive"))
    )
    (net (code "56") (name "PB6") (class "Default")
      (node (ref "IC2") (pin "42") (pinfunction "PB6_42") (pintype "bidirectional"))
    )
    (net (code "57") (name "PB7") (class "Default")
      (node (ref "IC2") (pin "43") (pinfunction "PB7_43") (pintype "bidirectional"))
    )
    (net (code "58") (name "PB8") (class "Default")
      (node (ref "IC2") (pin "45") (pinfunction "PB8_45") (pintype "bidirectional"))
      (node (ref "J1") (pin "16") (pinfunction "16_16") (pintype "passive"))
    )
    (net (code "59") (name "PB9") (class "Default")
      (node (ref "IC2") (pin "46") (pinfunction "PB9_46") (pintype "bidirectional"))
      (node (ref "J3") (pin "3") (pinfunction "3_3") (pintype "passive"))
    )
    (net (code "60") (name "PB10") (class "Default")
      (node (ref "IC2") (pin "21") (pinfunction "PB10_21") (pintype "bidirectional"))
      (node (ref "J1") (pin "5") (pinfunction "5_5") (pintype "passive"))
    )
    (net (code "61") (name "PB11") (class "Default")
      (node (ref "IC2") (pin "22") (pinfunction "PB11_22") (pintype "bidirectional"))
      (node (ref "J1") (pin "4") (pinfunction "4_4") (pintype "passive"))
    )
    (net (code "62") (name "PB12") (class "Default")
      (node (ref "IC2") (pin "25") (pinfunction "PB12_25") (pintype "bidirectional"))
      (node (ref "J1") (pin "3") (pinfunction "3_3") (pintype "passive"))
    )
    (net (code "63") (name "PB13") (class "Default")
      (node (ref "IC2") (pin "26") (pinfunction "PB13_26") (pintype "bidirectional"))
      (node (ref "J1") (pin "2") (pinfunction "2_2") (pintype "passive"))
    )
    (net (code "64") (name "PB14") (class "Default")
      (node (ref "IC2") (pin "27") (pinfunction "PB14_27") (pintype "bidirectional"))
      (node (ref "J1") (pin "1") (pinfunction "1_1") (pintype "passive"))
    )
    (net (code "65") (name "PB15") (class "Default")
      (node (ref "IC2") (pin "28") (pinfunction "PB15_28") (pintype "bidirectional"))
      (node (ref "J3") (pin "2") (pinfunction "2_2") (pintype "passive"))
    )
    (net (code "66") (name "PC13") (class "Default")
      (node (ref "IC2") (pin "2") (pinfunction "PC13-TAMPER-RTC_2") (pintype "bidirectional"))
    )
    (net (code "67") (name "PC14") (class "Default")
      (node (ref "IC2") (pin "3") (pinfunction "PC14-OSC32_IN_3") (pintype "bidirectional"))
      (node (ref "J1") (pin "12") (pinfunction "12_12") (pintype "passive"))
    )
    (net (code "68") (name "PC15") (class "Default")
      (node (ref "IC2") (pin "4") (pinfunction "PC15-OSC32_OUT_4") (pintype "bidirectional"))
      (node (ref "J3") (pin "4") (pinfunction "4_4") (pintype "passive"))
    )
    (net (code "69") (name "VBAT") (class "Default")
      (node (ref "IC2") (pin "1") (pinfunction "VBAT_1") (pintype "bidirectional"))
    )
    (net (code "70") (name "unconnected-(FAN-Pad3)") (class "Default")
      (node (ref "FAN") (pin "3") (pinfunction "3_3") (pintype "passive"))
    )
    (net (code "71") (name "unconnected-(IC1-1A-Pad2)") (class "Default")
      (node (ref "IC1") (pin "2") (pinfunction "1A_2") (pintype "input"))
    )
    (net (code "72") (name "unconnected-(IC1-1Y-Pad3)") (class "Default")
      (node (ref "IC1") (pin "3") (pinfunction "1Y_3") (pintype "output"))
    )
    (net (code "73") (name "unconnected-(IC1-2A-Pad7)") (class "Default")
      (node (ref "IC1") (pin "7") (pinfunction "2A_7") (pintype "input"))
    )
    (net (code "74") (name "unconnected-(IC1-2Y-Pad6)") (class "Default")
      (node (ref "IC1") (pin "6") (pinfunction "2Y_6") (pintype "output"))
    )
    (net (code "75") (name "unconnected-(USB-Pad1)") (class "Default")
      (node (ref "USB") (pin "1") (pinfunction "1_1") (pintype "passive"))
    )
    (net (code "76") (name "unconnected-(USB-Pad4)") (class "Default")
      (node (ref "USB") (pin "4") (pinfunction "4_4") (pintype "passive"))
    )
  )
)
